# Module_T_H_01v.net
KiCad netlist of a schematic drawn in EAGLE
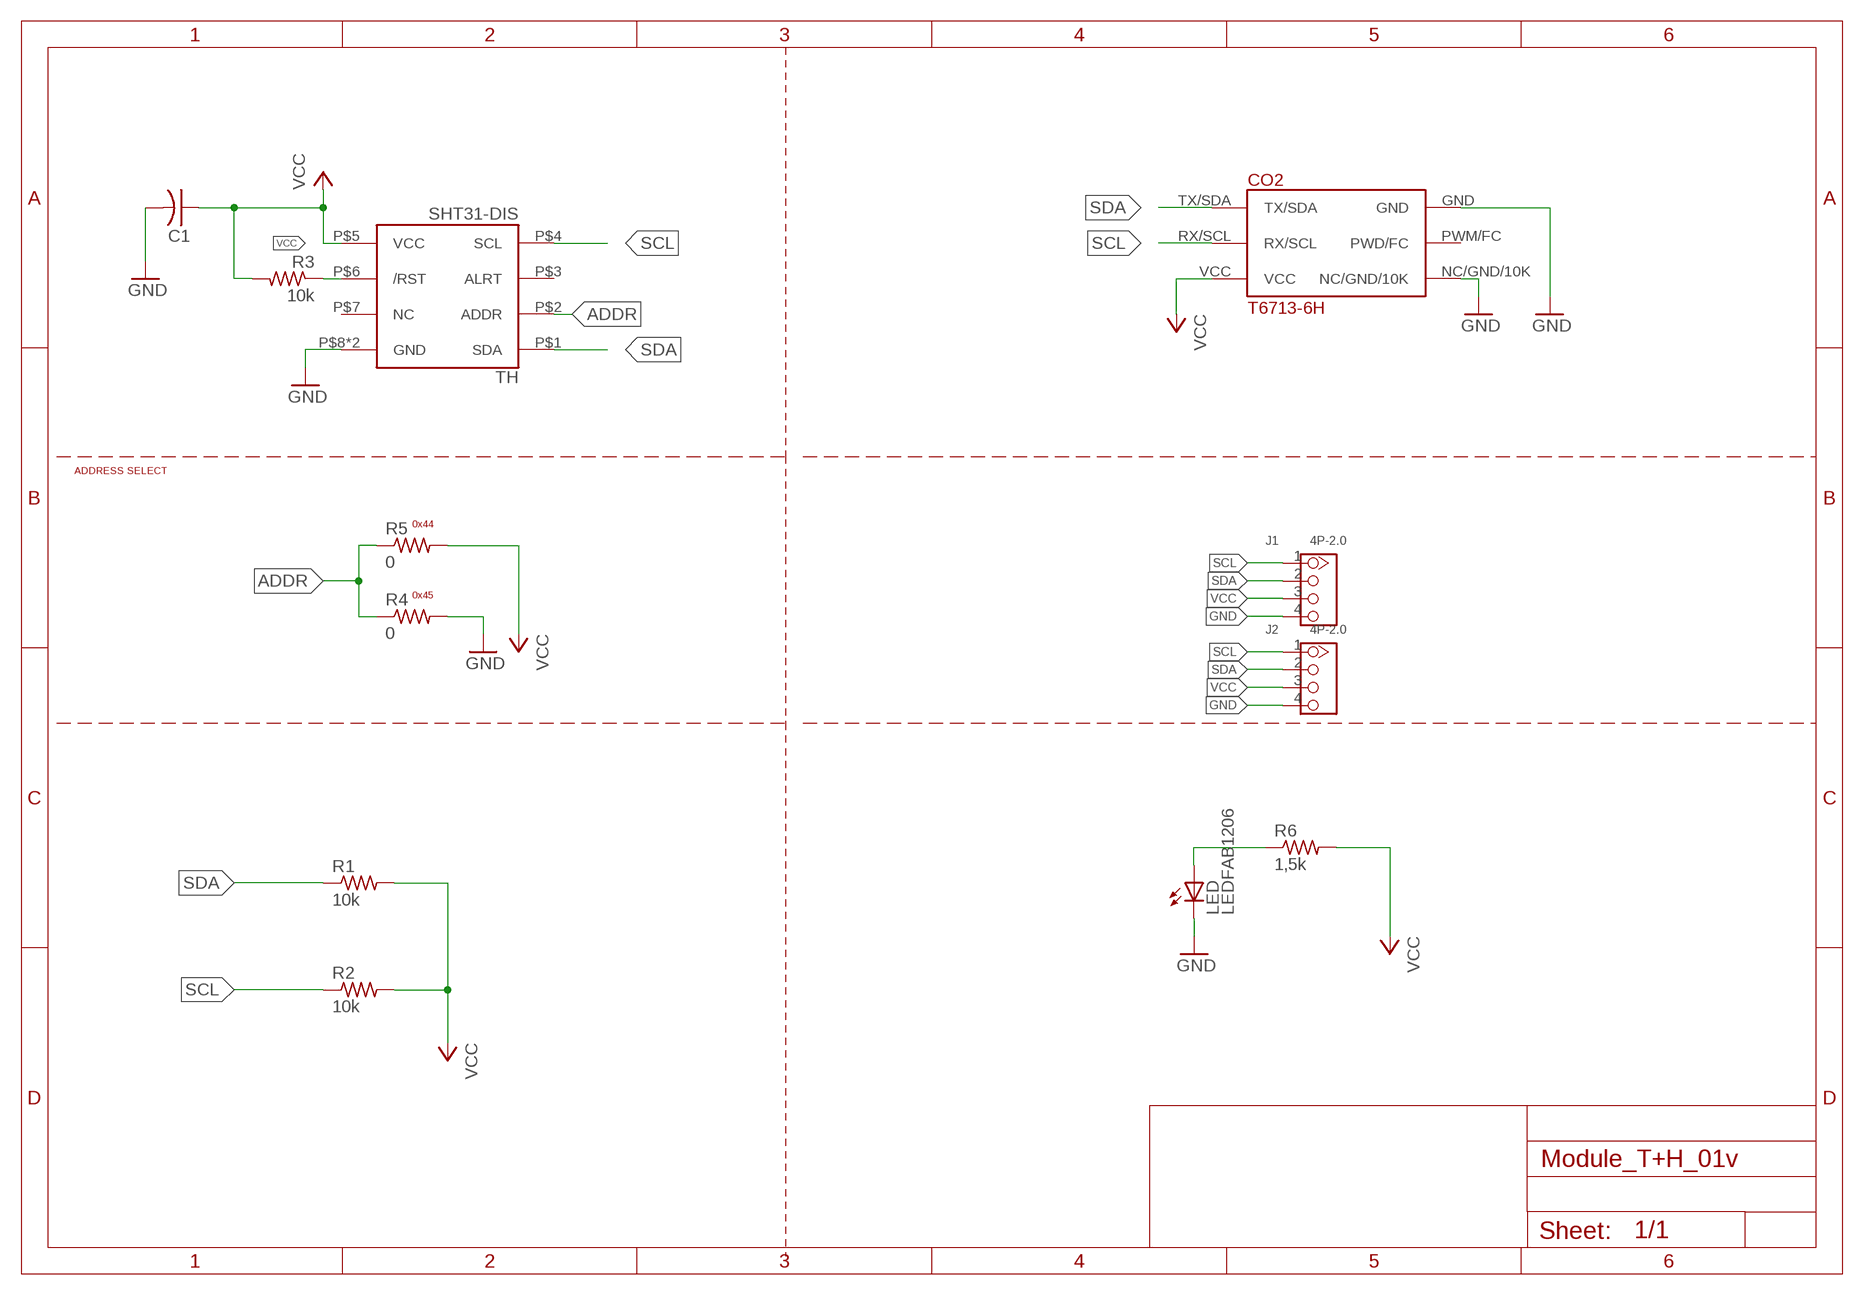
[diagram p0: schematic, sheet 1]

(export (version "E")
  (design (tool "Eeschema 10.0.6"))
  (components
    (comp (ref "C1")
      (value "CAP-US1206FAB")
      (footprint "eagle-import:C1206FAB")
      (libsource (lib "eagle-import") (part "CAP-US1206FAB"))
    )
    (comp (ref "CO2")
      (value "T6713-6H")
      (footprint "eagle-import:PINS")
      (libsource (lib "eagle-import") (part "T6713-6H"))
    )
    (comp (ref "J1")
      (value "4P-2.0")
      (footprint "eagle-import:HW4-2.0")
      (libsource (lib "eagle-import") (part "GROVE-CONNECTOR-DIP(4P-2.0)"))
    )
    (comp (ref "J2")
      (value "4P-2.0")
      (footprint "eagle-import:HW4-2.0")
      (libsource (lib "eagle-import") (part "GROVE-CONNECTOR-DIP(4P-2.0)"))
    )
    (comp (ref "LED")
      (value "LEDFAB1206")
      (footprint "eagle-import:LED1206FAB")
      (libsource (lib "eagle-import") (part "LEDFAB1206"))
    )
    (comp (ref "R1")
      (value "10k")
      (footprint "eagle-import:R1206FAB")
      (libsource (lib "eagle-import") (part "RES-US1206FAB"))
    )
    (comp (ref "R2")
      (value "10k")
      (footprint "eagle-import:R1206FAB")
      (libsource (lib "eagle-import") (part "RES-US1206FAB"))
    )
    (comp (ref "R3")
      (value "10k")
      (footprint "eagle-import:R1206FAB")
      (libsource (lib "eagle-import") (part "RES-US1206FAB"))
    )
    (comp (ref "R4")
      (value "0")
      (footprint "eagle-import:R1206FAB")
      (libsource (lib "eagle-import") (part "RES-US1206FAB"))
    )
    (comp (ref "R5")
      (value "0")
      (footprint "eagle-import:R1206FAB")
      (libsource (lib "eagle-import") (part "RES-US1206FAB"))
    )
    (comp (ref "R6")
      (value "1,5k")
      (footprint "eagle-import:R1206FAB")
      (libsource (lib "eagle-import") (part "RES-US1206FAB"))
    )
    (comp (ref "TH")
      (value "SHT31-DIS")
      (footprint "eagle-import:SHT3X")
      (libsource (lib "eagle-import") (part "SHT31-DIS"))
    )
  )
  (nets
    (net (code "1") (name "ADDR") (class "Default")
      (node (ref "R4") (pin "1") (pinfunction "1_1") (pintype "passive"))
      (node (ref "R5") (pin "1") (pinfunction "1_1") (pintype "passive"))
      (node (ref "TH") (pin "P$2") (pinfunction "ADDR_P$2") (pintype "bidirectional"))
    )
    (net (code "2") (name "GND") (class "Default")
      (node (ref "C1") (pin "2") (pinfunction "2_2") (pintype "passive"))
      (node (ref "CO2") (pin "GND") (pinfunction "GND_GND") (pintype "bidirectional"))
      (node (ref "CO2") (pin "NC/GND/10K") (pinfunction "NC/GND/10K_NC/GND/10K") (pintype "bidirectional"))
      (node (ref "J1") (pin "4") (pinfunction "4_4") (pintype "bidirectional"))
      (node (ref "J2") (pin "4") (pinfunction "4_4") (pintype "bidirectional"))
      (node (ref "LED") (pin "2") (pinfunction "C_2") (pintype "passive"))
      (node (ref "R4") (pin "2") (pinfunction "2_2") (pintype "passive"))
      (node (ref "TH") (pin "P$8") (pinfunction "GND_P$8") (pintype "bidirectional"))
      (node (ref "TH") (pin "PAD") (pinfunction "GND_PAD") (pintype "bidirectional"))
    )
    (net (code "3") (name "Net-(LED-A)") (class "Default")
      (node (ref "LED") (pin "1") (pinfunction "A_1") (pintype "passive"))
      (node (ref "R6") (pin "1") (pinfunction "1_1") (pintype "passive"))
    )
    (net (code "4") (name "Net-(TH-{slash}RST)") (class "Default")
      (node (ref "R3") (pin "1") (pinfunction "1_1") (pintype "passive"))
      (node (ref "TH") (pin "P$6") (pinfunction "/RST_P$6") (pintype "bidirectional"))
    )
    (net (code "5") (name "SCL") (class "Default")
      (node (ref "CO2") (pin "RX/SCL") (pinfunction "RX/SCL_RX/SCL") (pintype "bidirectional"))
      (node (ref "J1") (pin "1") (pinfunction "1_1") (pintype "bidirectional"))
      (node (ref "J2") (pin "1") (pinfunction "1_1") (pintype "bidirectional"))
      (node (ref "R2") (pin "1") (pinfunction "1_1") (pintype "passive"))
      (node (ref "TH") (pin "P$4") (pinfunction "SCL_P$4") (pintype "bidirectional"))
    )
    (net (code "6") (name "SDA") (class "Default")
      (node (ref "CO2") (pin "TX/SDA") (pinfunction "TX/SDA_TX/SDA") (pintype "bidirectional"))
      (node (ref "J1") (pin "2") (pinfunction "2_2") (pintype "bidirectional"))
      (node (ref "J2") (pin "2") (pinfunction "2_2") (pintype "bidirectional"))
      (node (ref "R1") (pin "1") (pinfunction "1_1") (pintype "passive"))
      (node (ref "TH") (pin "P$1") (pinfunction "SDA_P$1") (pintype "bidirectional"))
    )
    (net (code "7") (name "VCC") (class "Default")
      (node (ref "C1") (pin "1") (pinfunction "1_1") (pintype "passive"))
      (node (ref "CO2") (pin "VCC") (pinfunction "VCC_VCC") (pintype "bidirectional"))
      (node (ref "J1") (pin "3") (pinfunction "3_3") (pintype "bidirectional"))
      (node (ref "J2") (pin "3") (pinfunction "3_3") (pintype "bidirectional"))
      (node (ref "R1") (pin "2") (pinfunction "2_2") (pintype "passive"))
      (node (ref "R2") (pin "2") (pinfunction "2_2") (pintype "passive"))
      (node (ref "R3") (pin "2") (pinfunction "2_2") (pintype "passive"))
      (node (ref "R5") (pin "2") (pinfunction "2_2") (pintype "passive"))
      (node (ref "R6") (pin "2") (pinfunction "2_2") (pintype "passive"))
      (node (ref "TH") (pin "P$5") (pinfunction "VCC_P$5") (pintype "bidirectional"))
    )
    (net (code "8") (name "unconnected-(CO2-PWD{slash}FC-PadPWM{slash}FC)") (class "Default")
      (node (ref "CO2") (pin "PWM/FC") (pinfunction "PWD/FC_PWM/FC") (pintype "bidirectional"))
    )
    (net (code "9") (name "unconnected-(TH-ALRT-PadP$3)") (class "Default")
      (node (ref "TH") (pin "P$3") (pinfunction "ALRT_P$3") (pintype "bidirectional"))
    )
    (net (code "10") (name "unconnected-(TH-NC-PadP$7)") (class "Default")
      (node (ref "TH") (pin "P$7") (pinfunction "NC_P$7") (pintype "bidirectional"))
    )
  )
)
